# Spindle.net
KiCad netlist of a schematic drawn in Altium Designer
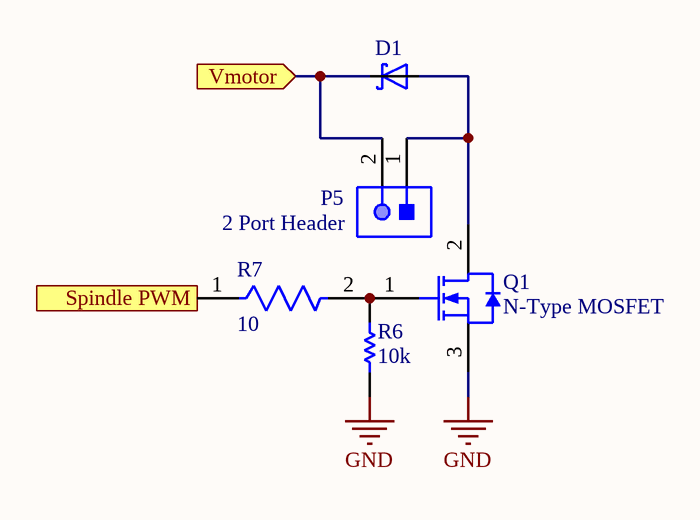
[diagram p0: Spindle.SchDoc]

(export (version "E")
  (design (tool "Eeschema 10.0.6"))
  (components
    (comp (ref "D1")
      (value "~")
      (footprint "SS34-1")
      (description "34 Position Cable Assembly Rectangular Socket to Cable 3.00' (914.40mm)")
      (fields (field (name "MP") "SS34A") (field (name "MF") "TE Connectivity"))
      (libsource (lib "JCULibrary_AS2_v2") (part "SS34-A"))
    )
    (comp (ref "P5")
      (value "2 Port Header")
      (footprint "JST-B2P-VH(LF)(SN)_V")
      (fields (field (name "TOLERANCE") "5%"))
      (libsource (lib "JCULibrary_AS2_v2") (part "JST_B2P-VH(LF)(SN)"))
    )
    (comp (ref "Q1")
      (value "BUK9635-55A,118")
      (footprint "NXP-SOT404_L")
      (description "3G PENTABAND 824-2170MHZ STRAIGH")
      (fields
        (field (name "MANUFACTURER") "Nexperia")
        (field (name "MANUFACTURER PART NUMBER") "N-Type MOSFET")
      )
      (libsource (lib "JCULibrary_AS2_v2") (part "BUK9635-55A,118"))
    )
    (comp (ref "R6")
      (value "10k")
      (footprint "RESC2013X60X35ML10T20")
      (description "Chip Resistor, 10 KOhm, +/- 5%, 0.125 W, -55 to 155 degC, 0805 (2012 Metric), RoHS, Tape and Reel")
      (fields (field (name "MANUFACTURER") "Yageo"))
      (libsource (lib "Altium Content Vault") (part "RES-2"))
    )
    (comp (ref "R7")
      (value "10")
      (footprint "FP-CRCW0805-e3-IPC_B")
      (description "RES Thick Film, 10Ω, 1%, 0.125W, 100ppm/°C, 0805")
      (fields (field (name "TOLERANCE") "1%"))
      (libsource (lib "Altium Content Vault") (part "1029c3af85768c4190bb7ad29bc67b5"))
    )
  )
  (nets
    (net (code "1") (name "/Spindle PWM") (class "Default")
      (node (ref "R7") (pin "1") (pinfunction "1_1") (pintype "passive"))
    )
    (net (code "2") (name "/Vmotor") (class "Default")
      (node (ref "D1") (pin "C") (pinfunction "C_C") (pintype "passive"))
      (node (ref "P5") (pin "2") (pinfunction "2_2") (pintype "passive"))
    )
    (net (code "3") (name "GND") (class "Default")
      (node (ref "Q1") (pin "3") (pinfunction "S_3") (pintype "passive"))
      (node (ref "R6") (pin "1") (pinfunction "1_1") (pintype "passive"))
    )
    (net (code "4") (name "Net-(Q1-D)") (class "Default")
      (node (ref "D1") (pin "A") (pinfunction "A_A") (pintype "passive"))
      (node (ref "P5") (pin "1") (pinfunction "1_1") (pintype "passive"))
      (node (ref "Q1") (pin "2") (pinfunction "D_2") (pintype "passive"))
    )
    (net (code "5") (name "Net-(Q1-G)") (class "Default")
      (node (ref "Q1") (pin "1") (pinfunction "G_1") (pintype "passive"))
      (node (ref "R6") (pin "2") (pinfunction "2_2") (pintype "passive"))
      (node (ref "R7") (pin "2") (pinfunction "2_2") (pintype "passive"))
    )
  )
)
